# D_rivateur.net
KiCad netlist of a schematic drawn in Altium Designer
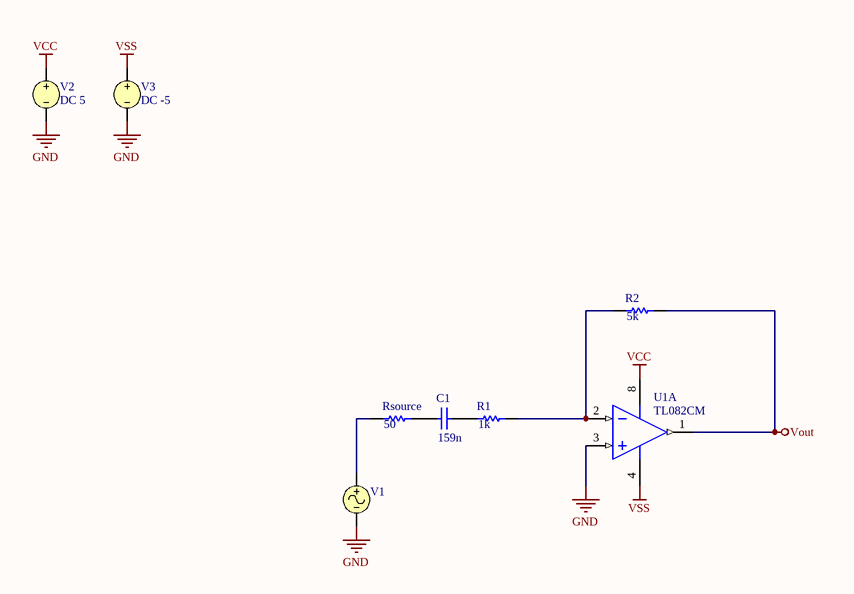
[diagram p0: Dérivateur.SchDoc]

(export (version "E")
  (design (tool "Eeschema 10.0.6"))
  (components
    (comp (ref "C1")
      (value "159n")
      (footprint "RAD-0.3")
      (description "Capacitor")
      (fields (field (name "Comment") "Cap") (field (name "PUBLISHER") "Altium Limited"))
      (libsource (lib "Miscellaneous Devices") (part "Cap"))
    )
    (comp (ref "R1")
      (value "1k")
      (footprint "AXIAL-0.3")
      (description "Resistor")
      (fields (field (name "Comment") "Res1") (field (name "PUBLISHER") "Altium Limited"))
      (libsource (lib "Miscellaneous Devices") (part "Res1"))
    )
    (comp (ref "R2")
      (value "5k")
      (footprint "AXIAL-0.3")
      (description "Resistor")
      (fields (field (name "Comment") "Res1") (field (name "PUBLISHER") "Altium Limited"))
      (libsource (lib "Miscellaneous Devices") (part "Res1"))
    )
    (comp (ref "Rsource")
      (value "50")
      (footprint "AXIAL-0.3")
      (description "Resistor")
      (fields (field (name "Comment") "Res1") (field (name "PUBLISHER") "Altium Limited"))
      (libsource (lib "Miscellaneous Devices") (part "Res1"))
    )
    (comp (ref "U1")
      (value "TL082CM")
      (footprint "M08A_N")
      (description "Wide Bandwidth Dual JFET Input Operational Amplifier, 8-pin Narrow SOIC")
      (fields
        (field (name "MANUFACTURER") "National Semiconductor")
        (field (name "PUBLISHER") "Altium Limited")
      )
      (libsource (lib "NSC Amplifier") (part "TL082CM"))
    )
    (comp (ref "V1")
      (value "PULSE(-5 5 0 0.05 0.05 1n 0.1 0)")
      (description "Sinusoidal Voltage Source")
      (fields (field (name "PUBLISHER") "Altium Limited"))
      (libsource (lib "Simulation Sources") (part "VSIN"))
    )
    (comp (ref "V2")
      (value "DC 5")
      (description "Voltage Source")
      (fields (field (name "PUBLISHER") "Altium Limited"))
      (libsource (lib "Simulation Sources") (part "VSRC"))
    )
    (comp (ref "V3")
      (value "DC -5")
      (description "Voltage Source")
      (fields (field (name "PUBLISHER") "Altium Limited"))
      (libsource (lib "Simulation Sources") (part "VSRC"))
    )
  )
  (nets
    (net (code "2") (name "GND") (class "Default")
      (node (ref "U1") (pin "3") (pinfunction "INA+_3") (pintype "input"))
      (node (ref "V1") (pin "2") (pinfunction "2_2") (pintype "passive"))
      (node (ref "V2") (pin "2") (pinfunction "2_2") (pintype "passive"))
      (node (ref "V3") (pin "2") (pinfunction "2_2") (pintype "passive"))
    )
    (net (code "3") (name "Net-(C1-Pad1)") (class "Default")
      (node (ref "C1") (pin "1") (pinfunction "1_1") (pintype "passive"))
      (node (ref "Rsource") (pin "2") (pinfunction "2_2") (pintype "passive"))
    )
    (net (code "4") (name "Net-(C1-Pad2)") (class "Default")
      (node (ref "C1") (pin "2") (pinfunction "2_2") (pintype "passive"))
      (node (ref "R1") (pin "1") (pinfunction "1_1") (pintype "passive"))
    )
    (net (code "5") (name "Net-(Rsource-Pad1)") (class "Default")
      (node (ref "Rsource") (pin "1") (pinfunction "1_1") (pintype "passive"))
      (node (ref "V1") (pin "1") (pinfunction "1_1") (pintype "passive"))
    )
    (net (code "6") (name "Net-(U1A-INA-)") (class "Default")
      (node (ref "R1") (pin "2") (pinfunction "2_2") (pintype "passive"))
      (node (ref "R2") (pin "1") (pinfunction "1_1") (pintype "passive"))
      (node (ref "U1") (pin "2") (pinfunction "INA-_2") (pintype "input"))
    )
    (net (code "7") (name "VCC") (class "Default")
      (node (ref "U1") (pin "8") (pinfunction "V+_8") (pintype "power_in"))
      (node (ref "V2") (pin "1") (pinfunction "1_1") (pintype "passive"))
    )
    (net (code "8") (name "VSS") (class "Default")
      (node (ref "U1") (pin "4") (pinfunction "V-_4") (pintype "power_in"))
      (node (ref "V3") (pin "1") (pinfunction "1_1") (pintype "passive"))
    )
    (net (code "9") (name "Vout") (class "Default")
      (node (ref "R2") (pin "2") (pinfunction "2_2") (pintype "passive"))
      (node (ref "U1") (pin "1") (pinfunction "OUTA_1") (pintype "output"))
    )
  )
)
